# PreOut.net
KiCad netlist of a schematic drawn in Altium Designer
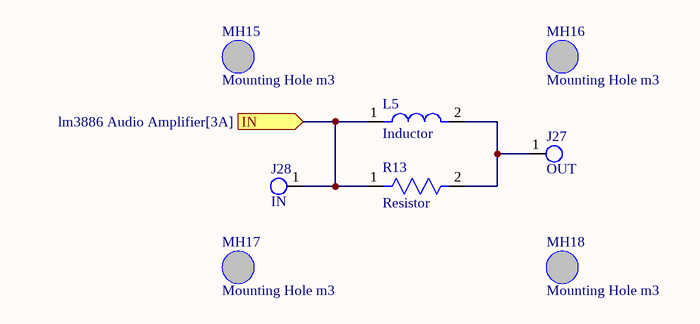
[diagram p0: PreOut.SchDoc]

(export (version "E")
  (design (tool "Eeschema 10.0.6"))
  (components
    (comp (ref "J27")
      (value "OUT")
      (footprint "Terminal 6.3mm male")
      (libsource (lib "lm3886 Schlib") (part "6.3mm Male Terminal"))
    )
    (comp (ref "J28")
      (value "IN")
      (footprint "Terminal 6.3mm male")
      (libsource (lib "lm3886 Schlib") (part "6.3mm Male Terminal"))
    )
    (comp (ref "L5")
      (value "Inductor")
      (footprint "Inductor p26")
      (libsource (lib "lm3886 Schlib") (part "Inductor"))
    )
    (comp (ref "MH15")
      (value "Mounting Hole m3")
      (footprint "Mounting Hole")
      (libsource (lib "lm3886 Schlib") (part "Mounting Hole m3"))
    )
    (comp (ref "MH16")
      (value "Mounting Hole m3")
      (footprint "Mounting Hole")
      (libsource (lib "lm3886 Schlib") (part "Mounting Hole m3"))
    )
    (comp (ref "MH17")
      (value "Mounting Hole m3")
      (footprint "Mounting Hole")
      (libsource (lib "lm3886 Schlib") (part "Mounting Hole m3"))
    )
    (comp (ref "MH18")
      (value "Mounting Hole m3")
      (footprint "Mounting Hole")
      (libsource (lib "lm3886 Schlib") (part "Mounting Hole m3"))
    )
    (comp (ref "R13")
      (value "Resistor")
      (footprint "Resistor 0823 5W")
      (libsource (lib "lm3886 Schlib") (part "Resistor"))
    )
  )
  (nets
    (net (code "1") (name "/IN") (class "Default")
      (node (ref "J28") (pin "1") (pintype "passive"))
      (node (ref "L5") (pin "1") (pintype "passive"))
      (node (ref "R13") (pin "1") (pintype "passive"))
    )
    (net (code "2") (name "Net-(J27-Pad1)") (class "Default")
      (node (ref "J27") (pin "1") (pintype "passive"))
      (node (ref "L5") (pin "2") (pintype "passive"))
      (node (ref "R13") (pin "2") (pintype "passive"))
    )
  )
)
